# dram.net
KiCad netlist of a schematic drawn in Altium Designer
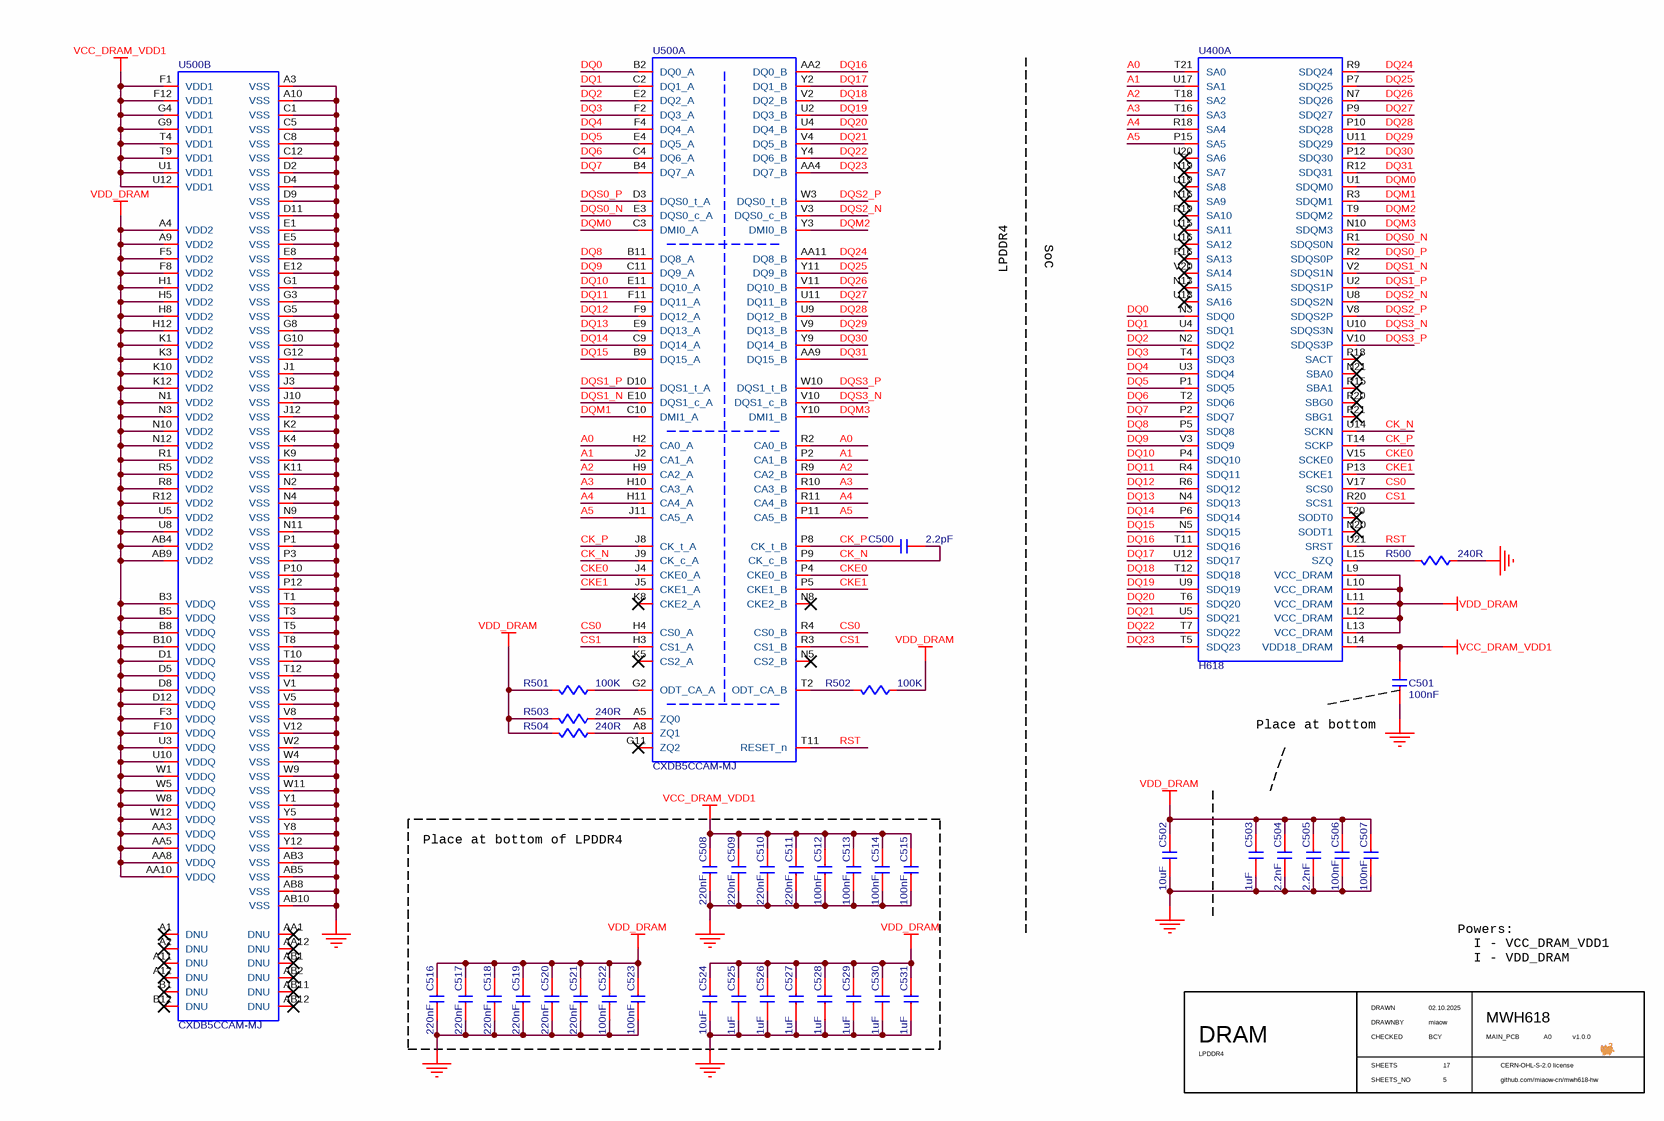
[diagram p0: dram.schdoc]

(export (version "E")
  (design (tool "Eeschema 10.0.6"))
  (components
    (comp (ref "C500")
      (value "2.2pF")
      (footprint "mw:C0201")
      (fields (field (name "VOLTAGE") "25V") (field (name "Comment") "C-NOMO"))
      (libsource (lib "mw") (part "C-NOMO"))
    )
    (comp (ref "C501")
      (value "100nF")
      (footprint "mw:C0201")
      (fields (field (name "VOLTAGE") "10V") (field (name "Comment") "C-NOMO"))
      (libsource (lib "mw") (part "C-NOMO"))
    )
    (comp (ref "C502")
      (value "10uF")
      (footprint "mw:C0402")
      (fields (field (name "VOLTAGE") "6.3V") (field (name "Comment") "C-NOMO"))
      (libsource (lib "mw") (part "C-NOMO"))
    )
    (comp (ref "C503")
      (value "1uF")
      (footprint "mw:C0201")
      (fields (field (name "VOLTAGE") "6.3V") (field (name "Comment") "C-NOMO"))
      (libsource (lib "mw") (part "C-NOMO"))
    )
    (comp (ref "C504")
      (value "2.2nF")
      (footprint "mw:C0201")
      (fields (field (name "VOLTAGE") "50V") (field (name "Comment") "C-NOMO"))
      (libsource (lib "mw") (part "C-NOMO"))
    )
    (comp (ref "C505")
      (value "2.2nF")
      (footprint "mw:C0201")
      (fields (field (name "VOLTAGE") "50V") (field (name "Comment") "C-NOMO"))
      (libsource (lib "mw") (part "C-NOMO"))
    )
    (comp (ref "C506")
      (value "100nF")
      (footprint "mw:C0201")
      (fields (field (name "VOLTAGE") "10V") (field (name "Comment") "C-NOMO"))
      (libsource (lib "mw") (part "C-NOMO"))
    )
    (comp (ref "C507")
      (value "100nF")
      (footprint "mw:C0201")
      (fields (field (name "VOLTAGE") "10V") (field (name "Comment") "C-NOMO"))
      (libsource (lib "mw") (part "C-NOMO"))
    )
    (comp (ref "C508")
      (value "220nF")
      (footprint "mw:C0201")
      (fields (field (name "VOLTAGE") "6.3V") (field (name "Comment") "C-NOMO"))
      (libsource (lib "mw") (part "C-NOMO"))
    )
    (comp (ref "C509")
      (value "220nF")
      (footprint "mw:C0201")
      (fields (field (name "VOLTAGE") "6.3V") (field (name "Comment") "C-NOMO"))
      (libsource (lib "mw") (part "C-NOMO"))
    )
    (comp (ref "C510")
      (value "220nF")
      (footprint "mw:C0201")
      (fields (field (name "VOLTAGE") "6.3V") (field (name "Comment") "C-NOMO"))
      (libsource (lib "mw") (part "C-NOMO"))
    )
    (comp (ref "C511")
      (value "220nF")
      (footprint "mw:C0201")
      (fields (field (name "VOLTAGE") "6.3V") (field (name "Comment") "C-NOMO"))
      (libsource (lib "mw") (part "C-NOMO"))
    )
    (comp (ref "C512")
      (value "100nF")
      (footprint "mw:C0201")
      (fields (field (name "VOLTAGE") "10V") (field (name "Comment") "C-NOMO"))
      (libsource (lib "mw") (part "C-NOMO"))
    )
    (comp (ref "C513")
      (value "100nF")
      (footprint "mw:C0201")
      (fields (field (name "VOLTAGE") "10V") (field (name "Comment") "C-NOMO"))
      (libsource (lib "mw") (part "C-NOMO"))
    )
    (comp (ref "C514")
      (value "100nF")
      (footprint "mw:C0201")
      (fields (field (name "VOLTAGE") "10V") (field (name "Comment") "C-NOMO"))
      (libsource (lib "mw") (part "C-NOMO"))
    )
    (comp (ref "C515")
      (value "100nF")
      (footprint "mw:C0201")
      (fields (field (name "VOLTAGE") "10V") (field (name "Comment") "C-NOMO"))
      (libsource (lib "mw") (part "C-NOMO"))
    )
    (comp (ref "C516")
      (value "220nF")
      (footprint "mw:C0201")
      (fields (field (name "VOLTAGE") "6.3V") (field (name "Comment") "C-NOMO"))
      (libsource (lib "mw") (part "C-NOMO"))
    )
    (comp (ref "C517")
      (value "220nF")
      (footprint "mw:C0201")
      (fields (field (name "VOLTAGE") "6.3V") (field (name "Comment") "C-NOMO"))
      (libsource (lib "mw") (part "C-NOMO"))
    )
    (comp (ref "C518")
      (value "220nF")
      (footprint "mw:C0201")
      (fields (field (name "VOLTAGE") "6.3V") (field (name "Comment") "C-NOMO"))
      (libsource (lib "mw") (part "C-NOMO"))
    )
    (comp (ref "C519")
      (value "220nF")
      (footprint "mw:C0201")
      (fields (field (name "VOLTAGE") "6.3V") (field (name "Comment") "C-NOMO"))
      (libsource (lib "mw") (part "C-NOMO"))
    )
    (comp (ref "C520")
      (value "220nF")
      (footprint "mw:C0201")
      (fields (field (name "VOLTAGE") "6.3V") (field (name "Comment") "C-NOMO"))
      (libsource (lib "mw") (part "C-NOMO"))
    )
    (comp (ref "C521")
      (value "220nF")
      (footprint "mw:C0201")
      (fields (field (name "VOLTAGE") "6.3V") (field (name "Comment") "C-NOMO"))
      (libsource (lib "mw") (part "C-NOMO"))
    )
    (comp (ref "C522")
      (value "100nF")
      (footprint "mw:C0201")
      (fields (field (name "VOLTAGE") "10V") (field (name "Comment") "C-NOMO"))
      (libsource (lib "mw") (part "C-NOMO"))
    )
    (comp (ref "C523")
      (value "100nF")
      (footprint "mw:C0201")
      (fields (field (name "VOLTAGE") "10V") (field (name "Comment") "C-NOMO"))
      (libsource (lib "mw") (part "C-NOMO"))
    )
    (comp (ref "C524")
      (value "10uF")
      (footprint "mw:C0402")
      (fields (field (name "VOLTAGE") "6.3V") (field (name "Comment") "C-NOMO"))
      (libsource (lib "mw") (part "C-NOMO"))
    )
    (comp (ref "C525")
      (value "1uF")
      (footprint "mw:C0201")
      (fields (field (name "VOLTAGE") "6.3V") (field (name "Comment") "C-NOMO"))
      (libsource (lib "mw") (part "C-NOMO"))
    )
    (comp (ref "C526")
      (value "1uF")
      (footprint "mw:C0201")
      (fields (field (name "VOLTAGE") "6.3V") (field (name "Comment") "C-NOMO"))
      (libsource (lib "mw") (part "C-NOMO"))
    )
    (comp (ref "C527")
      (value "1uF")
      (footprint "mw:C0201")
      (fields (field (name "VOLTAGE") "6.3V") (field (name "Comment") "C-NOMO"))
      (libsource (lib "mw") (part "C-NOMO"))
    )
    (comp (ref "C528")
      (value "1uF")
      (footprint "mw:C0201")
      (fields (field (name "VOLTAGE") "6.3V") (field (name "Comment") "C-NOMO"))
      (libsource (lib "mw") (part "C-NOMO"))
    )
    (comp (ref "C529")
      (value "1uF")
      (footprint "mw:C0201")
      (fields (field (name "VOLTAGE") "6.3V") (field (name "Comment") "C-NOMO"))
      (libsource (lib "mw") (part "C-NOMO"))
    )
    (comp (ref "C530")
      (value "1uF")
      (footprint "mw:C0201")
      (fields (field (name "VOLTAGE") "6.3V") (field (name "Comment") "C-NOMO"))
      (libsource (lib "mw") (part "C-NOMO"))
    )
    (comp (ref "C531")
      (value "1uF")
      (footprint "mw:C0201")
      (fields (field (name "VOLTAGE") "6.3V") (field (name "Comment") "C-NOMO"))
      (libsource (lib "mw") (part "C-NOMO"))
    )
    (comp (ref "R500")
      (value "240R")
      (footprint "mw:R0402")
      (fields (field (name "Comment") "R"))
      (libsource (lib "mw") (part "R"))
    )
    (comp (ref "R501")
      (value "100K")
      (footprint "mw:R0402")
      (fields (field (name "Comment") "R"))
      (libsource (lib "mw") (part "R"))
    )
    (comp (ref "R502")
      (value "100K")
      (footprint "mw:R0402")
      (fields (field (name "Comment") "R"))
      (libsource (lib "mw") (part "R"))
    )
    (comp (ref "R503")
      (value "240R")
      (footprint "mw:R0402")
      (fields (field (name "Comment") "R"))
      (libsource (lib "mw") (part "R"))
    )
    (comp (ref "R504")
      (value "240R")
      (footprint "mw:R0402")
      (fields (field (name "Comment") "R"))
      (libsource (lib "mw") (part "R"))
    )
    (comp (ref "U400")
      (value "H618")
      (footprint "mw:H618")
      (description "SOC")
      (libsource (lib "mw") (part "H618"))
    )
    (comp (ref "U500")
      (value "CXDB5CCAM-MJ")
      (footprint "mw:CXDB5CCAM-MJ")
      (description "DDR - LPDDR4")
      (libsource (lib "mw") (part "CXDB5CCAM-MJ"))
    )
  )
  (nets
    (net (code "1") (name "/A0") (class "Default")
      (node (ref "U400") (pin "T21") (pinfunction "SA0_T21") (pintype "passive"))
      (node (ref "U500") (pin "H2") (pinfunction "CA0_A_H2") (pintype "passive"))
      (node (ref "U500") (pin "R2") (pinfunction "CA0_B_R2") (pintype "passive"))
    )
    (net (code "2") (name "/A1") (class "Default")
      (node (ref "U400") (pin "U17") (pinfunction "SA1_U17") (pintype "passive"))
      (node (ref "U500") (pin "J2") (pinfunction "CA1_A_J2") (pintype "passive"))
      (node (ref "U500") (pin "P2") (pinfunction "CA1_B_P2") (pintype "passive"))
    )
    (net (code "3") (name "/A2") (class "Default")
      (node (ref "U400") (pin "T18") (pinfunction "SA2_T18") (pintype "passive"))
      (node (ref "U500") (pin "H9") (pinfunction "CA2_A_H9") (pintype "passive"))
      (node (ref "U500") (pin "R9") (pinfunction "CA2_B_R9") (pintype "passive"))
    )
    (net (code "4") (name "/A3") (class "Default")
      (node (ref "U400") (pin "T16") (pinfunction "SA3_T16") (pintype "passive"))
      (node (ref "U500") (pin "H10") (pinfunction "CA3_A_H10") (pintype "passive"))
      (node (ref "U500") (pin "R10") (pinfunction "CA3_B_R10") (pintype "passive"))
    )
    (net (code "5") (name "/A4") (class "Default")
      (node (ref "U400") (pin "R18") (pinfunction "SA4_R18") (pintype "passive"))
      (node (ref "U500") (pin "H11") (pinfunction "CA4_A_H11") (pintype "passive"))
      (node (ref "U500") (pin "R11") (pinfunction "CA4_B_R11") (pintype "passive"))
    )
    (net (code "6") (name "/A5") (class "Default")
      (node (ref "U400") (pin "P15") (pinfunction "SA5_P15") (pintype "passive"))
      (node (ref "U500") (pin "J11") (pinfunction "CA5_A_J11") (pintype "passive"))
      (node (ref "U500") (pin "P11") (pinfunction "CA5_B_P11") (pintype "passive"))
    )
    (net (code "7") (name "/CKE0") (class "Default")
      (node (ref "U400") (pin "V15") (pinfunction "SCKE0_V15") (pintype "passive"))
      (node (ref "U500") (pin "J4") (pinfunction "CKE0_A_J4") (pintype "passive"))
      (node (ref "U500") (pin "P4") (pinfunction "CKE0_B_P4") (pintype "passive"))
    )
    (net (code "8") (name "/CKE1") (class "Default")
      (node (ref "U400") (pin "P13") (pinfunction "SCKE1_P13") (pintype "passive"))
      (node (ref "U500") (pin "J5") (pinfunction "CKE1_A_J5") (pintype "passive"))
      (node (ref "U500") (pin "P5") (pinfunction "CKE1_B_P5") (pintype "passive"))
    )
    (net (code "9") (name "/CK_N") (class "Default")
      (node (ref "C500") (pin "1") (pinfunction "1_1") (pintype "passive"))
      (node (ref "U400") (pin "U14") (pinfunction "SCKN_U14") (pintype "passive"))
      (node (ref "U500") (pin "J9") (pinfunction "CK_c_A_J9") (pintype "passive"))
      (node (ref "U500") (pin "P9") (pinfunction "CK_c_B_P9") (pintype "passive"))
    )
    (net (code "10") (name "/CK_P") (class "Default")
      (node (ref "C500") (pin "2") (pinfunction "2_2") (pintype "passive"))
      (node (ref "U400") (pin "T14") (pinfunction "SCKP_T14") (pintype "passive"))
      (node (ref "U500") (pin "J8") (pinfunction "CK_t_A_J8") (pintype "passive"))
      (node (ref "U500") (pin "P8") (pinfunction "CK_t_B_P8") (pintype "passive"))
    )
    (net (code "11") (name "/CS0") (class "Default")
      (node (ref "U400") (pin "V17") (pinfunction "SCS0_V17") (pintype "passive"))
      (node (ref "U500") (pin "H4") (pinfunction "CS0_A_H4") (pintype "passive"))
      (node (ref "U500") (pin "R4") (pinfunction "CS0_B_R4") (pintype "passive"))
    )
    (net (code "12") (name "/CS1") (class "Default")
      (node (ref "U400") (pin "R20") (pinfunction "SCS1_R20") (pintype "passive"))
      (node (ref "U500") (pin "H3") (pinfunction "CS1_A_H3") (pintype "passive"))
      (node (ref "U500") (pin "R3") (pinfunction "CS1_B_R3") (pintype "passive"))
    )
    (net (code "13") (name "/DQ0") (class "Default")
      (node (ref "U400") (pin "N3") (pinfunction "SDQ0_N3") (pintype "passive"))
      (node (ref "U500") (pin "B2") (pinfunction "DQ0_A_B2") (pintype "passive"))
    )
    (net (code "14") (name "/DQ1") (class "Default")
      (node (ref "U400") (pin "U4") (pinfunction "SDQ1_U4") (pintype "passive"))
      (node (ref "U500") (pin "C2") (pinfunction "DQ1_A_C2") (pintype "passive"))
    )
    (net (code "15") (name "/DQ2") (class "Default")
      (node (ref "U400") (pin "N2") (pinfunction "SDQ2_N2") (pintype "passive"))
      (node (ref "U500") (pin "E2") (pinfunction "DQ2_A_E2") (pintype "passive"))
    )
    (net (code "16") (name "/DQ3") (class "Default")
      (node (ref "U400") (pin "T4") (pinfunction "SDQ3_T4") (pintype "passive"))
      (node (ref "U500") (pin "F2") (pinfunction "DQ3_A_F2") (pintype "passive"))
    )
    (net (code "17") (name "/DQ4") (class "Default")
      (node (ref "U400") (pin "U3") (pinfunction "SDQ4_U3") (pintype "passive"))
      (node (ref "U500") (pin "F4") (pinfunction "DQ4_A_F4") (pintype "passive"))
    )
    (net (code "18") (name "/DQ5") (class "Default")
      (node (ref "U400") (pin "P1") (pinfunction "SDQ5_P1") (pintype "passive"))
      (node (ref "U500") (pin "E4") (pinfunction "DQ5_A_E4") (pintype "passive"))
    )
    (net (code "19") (name "/DQ6") (class "Default")
      (node (ref "U400") (pin "T2") (pinfunction "SDQ6_T2") (pintype "passive"))
      (node (ref "U500") (pin "C4") (pinfunction "DQ6_A_C4") (pintype "passive"))
    )
    (net (code "20") (name "/DQ7") (class "Default")
      (node (ref "U400") (pin "P2") (pinfunction "SDQ7_P2") (pintype "passive"))
      (node (ref "U500") (pin "B4") (pinfunction "DQ7_A_B4") (pintype "passive"))
    )
    (net (code "21") (name "/DQ8") (class "Default")
      (node (ref "U400") (pin "P5") (pinfunction "SDQ8_P5") (pintype "passive"))
      (node (ref "U500") (pin "B11") (pinfunction "DQ8_A_B11") (pintype "passive"))
    )
    (net (code "22") (name "/DQ9") (class "Default")
      (node (ref "U400") (pin "V3") (pinfunction "SDQ9_V3") (pintype "passive"))
      (node (ref "U500") (pin "C11") (pinfunction "DQ9_A_C11") (pintype "passive"))
    )
    (net (code "23") (name "/DQ10") (class "Default")
      (node (ref "U400") (pin "P4") (pinfunction "SDQ10_P4") (pintype "passive"))
      (node (ref "U500") (pin "E11") (pinfunction "DQ10_A_E11") (pintype "passive"))
    )
    (net (code "24") (name "/DQ11") (class "Default")
      (node (ref "U400") (pin "R4") (pinfunction "SDQ11_R4") (pintype "passive"))
      (node (ref "U500") (pin "F11") (pinfunction "DQ11_A_F11") (pintype "passive"))
    )
    (net (code "25") (name "/DQ12") (class "Default")
      (node (ref "U400") (pin "R6") (pinfunction "SDQ12_R6") (pintype "passive"))
      (node (ref "U500") (pin "F9") (pinfunction "DQ12_A_F9") (pintype "passive"))
    )
    (net (code "26") (name "/DQ13") (class "Default")
      (node (ref "U400") (pin "N4") (pinfunction "SDQ13_N4") (pintype "passive"))
      (node (ref "U500") (pin "E9") (pinfunction "DQ13_A_E9") (pintype "passive"))
    )
    (net (code "27") (name "/DQ14") (class "Default")
      (node (ref "U400") (pin "P6") (pinfunction "SDQ14_P6") (pintype "passive"))
      (node (ref "U500") (pin "C9") (pinfunction "DQ14_A_C9") (pintype "passive"))
    )
    (net (code "28") (name "/DQ15") (class "Default")
      (node (ref "U400") (pin "N5") (pinfunction "SDQ15_N5") (pintype "passive"))
      (node (ref "U500") (pin "B9") (pinfunction "DQ15_A_B9") (pintype "passive"))
    )
    (net (code "29") (name "/DQ16") (class "Default")
      (node (ref "U400") (pin "T11") (pinfunction "SDQ16_T11") (pintype "passive"))
      (node (ref "U500") (pin "AA2") (pinfunction "DQ0_B_AA2") (pintype "passive"))
    )
    (net (code "30") (name "/DQ17") (class "Default")
      (node (ref "U400") (pin "U12") (pinfunction "SDQ17_U12") (pintype "passive"))
      (node (ref "U500") (pin "Y2") (pinfunction "DQ1_B_Y2") (pintype "passive"))
    )
    (net (code "31") (name "/DQ18") (class "Default")
      (node (ref "U400") (pin "T12") (pinfunction "SDQ18_T12") (pintype "passive"))
      (node (ref "U500") (pin "V2") (pinfunction "DQ2_B_V2") (pintype "passive"))
    )
    (net (code "32") (name "/DQ19") (class "Default")
      (node (ref "U400") (pin "U9") (pinfunction "SDQ19_U9") (pintype "passive"))
      (node (ref "U500") (pin "U2") (pinfunction "DQ3_B_U2") (pintype "passive"))
    )
    (net (code "33") (name "/DQ20") (class "Default")
      (node (ref "U400") (pin "T6") (pinfunction "SDQ20_T6") (pintype "passive"))
      (node (ref "U500") (pin "U4") (pinfunction "DQ4_B_U4") (pintype "passive"))
    )
    (net (code "34") (name "/DQ21") (class "Default")
      (node (ref "U400") (pin "U5") (pinfunction "SDQ21_U5") (pintype "passive"))
      (node (ref "U500") (pin "V4") (pinfunction "DQ5_B_V4") (pintype "passive"))
    )
    (net (code "35") (name "/DQ22") (class "Default")
      (node (ref "U400") (pin "T7") (pinfunction "SDQ22_T7") (pintype "passive"))
      (node (ref "U500") (pin "Y4") (pinfunction "DQ6_B_Y4") (pintype "passive"))
    )
    (net (code "36") (name "/DQ23") (class "Default")
      (node (ref "U400") (pin "T5") (pinfunction "SDQ23_T5") (pintype "passive"))
      (node (ref "U500") (pin "AA4") (pinfunction "DQ7_B_AA4") (pintype "passive"))
    )
    (net (code "37") (name "/DQ24") (class "Default")
      (node (ref "U400") (pin "R9") (pinfunction "SDQ24_R9") (pintype "passive"))
      (node (ref "U500") (pin "AA11") (pinfunction "DQ8_B_AA11") (pintype "passive"))
    )
    (net (code "38") (name "/DQ25") (class "Default")
      (node (ref "U400") (pin "P7") (pinfunction "SDQ25_P7") (pintype "passive"))
      (node (ref "U500") (pin "Y11") (pinfunction "DQ9_B_Y11") (pintype "passive"))
    )
    (net (code "39") (name "/DQ26") (class "Default")
      (node (ref "U400") (pin "N7") (pinfunction "SDQ26_N7") (pintype "passive"))
      (node (ref "U500") (pin "V11") (pinfunction "DQ10_B_V11") (pintype "passive"))
    )
    (net (code "40") (name "/DQ27") (class "Default")
      (node (ref "U400") (pin "P9") (pinfunction "SDQ27_P9") (pintype "passive"))
      (node (ref "U500") (pin "U11") (pinfunction "DQ11_B_U11") (pintype "passive"))
    )
    (net (code "41") (name "/DQ28") (class "Default")
      (node (ref "U400") (pin "P10") (pinfunction "SDQ28_P10") (pintype "passive"))
      (node (ref "U500") (pin "U9") (pinfunction "DQ12_B_U9") (pintype "passive"))
    )
    (net (code "42") (name "/DQ29") (class "Default")
      (node (ref "U400") (pin "U11") (pinfunction "SDQ29_U11") (pintype "passive"))
      (node (ref "U500") (pin "V9") (pinfunction "DQ13_B_V9") (pintype "passive"))
    )
    (net (code "43") (name "/DQ30") (class "Default")
      (node (ref "U400") (pin "P12") (pinfunction "SDQ30_P12") (pintype "passive"))
      (node (ref "U500") (pin "Y9") (pinfunction "DQ14_B_Y9") (pintype "passive"))
    )
    (net (code "44") (name "/DQ31") (class "Default")
      (node (ref "U400") (pin "R12") (pinfunction "SDQ31_R12") (pintype "passive"))
      (node (ref "U500") (pin "AA9") (pinfunction "DQ15_B_AA9") (pintype "passive"))
    )
    (net (code "45") (name "/DQM0") (class "Default")
      (node (ref "U400") (pin "U1") (pinfunction "SDQM0_U1") (pintype "passive"))
      (node (ref "U500") (pin "C3") (pinfunction "DMI0_A_C3") (pintype "passive"))
    )
    (net (code "46") (name "/DQM1") (class "Default")
      (node (ref "U400") (pin "R3") (pinfunction "SDQM1_R3") (pintype "passive"))
      (node (ref "U500") (pin "C10") (pinfunction "DMI1_A_C10") (pintype "passive"))
    )
    (net (code "47") (name "/DQM2") (class "Default")
      (node (ref "U400") (pin "T9") (pinfunction "SDQM2_T9") (pintype "passive"))
      (node (ref "U500") (pin "Y3") (pinfunction "DMI0_B_Y3") (pintype "passive"))
    )
    (net (code "48") (name "/DQM3") (class "Default")
      (node (ref "U400") (pin "N10") (pinfunction "SDQM3_N10") (pintype "passive"))
      (node (ref "U500") (pin "Y10") (pinfunction "DMI1_B_Y10") (pintype "passive"))
    )
    (net (code "49") (name "/DQS0_N") (class "Default")
      (node (ref "U400") (pin "R1") (pinfunction "SDQS0N_R1") (pintype "passive"))
      (node (ref "U500") (pin "E3") (pinfunction "DQS0_c_A_E3") (pintype "passive"))
    )
    (net (code "50") (name "/DQS0_P") (class "Default")
      (node (ref "U400") (pin "R2") (pinfunction "SDQS0P_R2") (pintype "passive"))
      (node (ref "U500") (pin "D3") (pinfunction "DQS0_t_A_D3") (pintype "passive"))
    )
    (net (code "51") (name "/DQS1_N") (class "Default")
      (node (ref "U400") (pin "V2") (pinfunction "SDQS1N_V2") (pintype "passive"))
      (node (ref "U500") (pin "E10") (pinfunction "DQS1_c_A_E10") (pintype "passive"))
    )
    (net (code "52") (name "/DQS1_P") (class "Default")
      (node (ref "U400") (pin "U2") (pinfunction "SDQS1P_U2") (pintype "passive"))
      (node (ref "U500") (pin "D10") (pinfunction "DQS1_t_A_D10") (pintype "passive"))
    )
    (net (code "53") (name "/DQS2_N") (class "Default")
      (node (ref "U400") (pin "U8") (pinfunction "SDQS2N_U8") (pintype "passive"))
      (node (ref "U500") (pin "V3") (pinfunction "DQS0_c_B_V3") (pintype "passive"))
    )
    (net (code "54") (name "/DQS2_P") (class "Default")
      (node (ref "U400") (pin "V8") (pinfunction "SDQS2P_V8") (pintype "passive"))
      (node (ref "U500") (pin "W3") (pinfunction "DQS0_t_B_W3") (pintype "passive"))
    )
    (net (code "55") (name "/DQS3_N") (class "Default")
      (node (ref "U400") (pin "U10") (pinfunction "SDQS3N_U10") (pintype "passive"))
      (node (ref "U500") (pin "V10") (pinfunction "DQS1_c_B_V10") (pintype "passive"))
    )
    (net (code "56") (name "/DQS3_P") (class "Default")
      (node (ref "U400") (pin "V10") (pinfunction "SDQS3P_V10") (pintype "passive"))
      (node (ref "U500") (pin "W10") (pinfunction "DQS1_t_B_W10") (pintype "passive"))
    )
    (net (code "57") (name "/RST") (class "Default")
      (node (ref "U400") (pin "U21") (pinfunction "SRST_U21") (pintype "passive"))
      (node (ref "U500") (pin "T11") (pinfunction "RESET_n_T11") (pintype "passive"))
    )
    (net (code "58") (name "GND") (class "Default")
      (node (ref "C501") (pin "1") (pinfunction "1_1") (pintype "passive"))
      (node (ref "C502") (pin "1") (pinfunction "1_1") (pintype "passive"))
      (node (ref "C503") (pin "1") (pinfunction "1_1") (pintype "passive"))
      (node (ref "C504") (pin "1") (pinfunction "1_1") (pintype "passive"))
      (node (ref "C505") (pin "1") (pinfunction "1_1") (pintype "passive"))
      (node (ref "C506") (pin "1") (pinfunction "1_1") (pintype "passive"))
      (node (ref "C507") (pin "1") (pinfunction "1_1") (pintype "passive"))
      (node (ref "C508") (pin "1") (pinfunction "1_1") (pintype "passive"))
      (node (ref "C509") (pin "1") (pinfunction "1_1") (pintype "passive"))
      (node (ref "C510") (pin "1") (pinfunction "1_1") (pintype "passive"))
      (node (ref "C511") (pin "1") (pinfunction "1_1") (pintype "passive"))
      (node (ref "C512") (pin "1") (pinfunction "1_1") (pintype "passive"))
      (node (ref "C513") (pin "1") (pinfunction "1_1") (pintype "passive"))
      (node (ref "C514") (pin "1") (pinfunction "1_1") (pintype "passive"))
      (node (ref "C515") (pin "1") (pinfunction "1_1") (pintype "passive"))
      (node (ref "C516") (pin "1") (pinfunction "1_1") (pintype "passive"))
      (node (ref "C517") (pin "1") (pinfunction "1_1") (pintype "passive"))
      (node (ref "C518") (pin "1") (pinfunction "1_1") (pintype "passive"))
      (node (ref "C519") (pin "1") (pinfunction "1_1") (pintype "passive"))
      (node (ref "C520") (pin "1") (pinfunction "1_1") (pintype "passive"))
      (node (ref "C521") (pin "1") (pinfunction "1_1") (pintype "passive"))
      (node (ref "C522") (pin "1") (pinfunction "1_1") (pintype "passive"))
      (node (ref "C523") (pin "1") (pinfunction "1_1") (pintype "passive"))
      (node (ref "C524") (pin "1") (pinfunction "1_1") (pintype "passive"))
      (node (ref "C525") (pin "1") (pinfunction "1_1") (pintype "passive"))
      (node (ref "C526") (pin "1") (pinfunction "1_1") (pintype "passive"))
      (node (ref "C527") (pin "1") (pinfunction "1_1") (pintype "passive"))
      (node (ref "C528") (pin "1") (pinfunction "1_1") (pintype "passive"))
      (node (ref "C529") (pin "1") (pinfunction "1_1") (pintype "passive"))
      (node (ref "C530") (pin "1") (pinfunction "1_1") (pintype "passive"))
      (node (ref "C531") (pin "1") (pinfunction "1_1") (pintype "passive"))
      (node (ref "R500") (pin "2") (pinfunction "2_2") (pintype "passive"))
      (node (ref "U500") (pin "A10") (pinfunction "VSS_A10") (pintype "passive"))
      (node (ref "U500") (pin "A3") (pinfunction "VSS_A3") (pintype "passive"))
      (node (ref "U500") (pin "AB10") (pinfunction "VSS_AB10") (pintype "passive"))
      (node (ref "U500") (pin "AB3") (pinfunction "VSS_AB3") (pintype "passive"))
      (node (ref "U500") (pin "AB5") (pinfunction "VSS_AB5") (pintype "passive"))
      (node (ref "U500") (pin "AB8") (pinfunction "VSS_AB8") (pintype "passive"))
      (node (ref "U500") (pin "C1") (pinfunction "VSS_C1") (pintype "passive"))
      (node (ref "U500") (pin "C12") (pinfunction "VSS_C12") (pintype "passive"))
      (node (ref "U500") (pin "C5") (pinfunction "VSS_C5") (pintype "passive"))
      (node (ref "U500") (pin "C8") (pinfunction "VSS_C8") (pintype "passive"))
      (node (ref "U500") (pin "D11") (pinfunction "VSS_D11") (pintype "passive"))
      (node (ref "U500") (pin "D2") (pinfunction "VSS_D2") (pintype "passive"))
      (node (ref "U500") (pin "D4") (pinfunction "VSS_D4") (pintype "passive"))
      (node (ref "U500") (pin "D9") (pinfunction "VSS_D9") (pintype "passive"))
      (node (ref "U500") (pin "E1") (pinfunction "VSS_E1") (pintype "passive"))
      (node (ref "U500") (pin "E12") (pinfunction "VSS_E12") (pintype "passive"))
      (node (ref "U500") (pin "E5") (pinfunction "VSS_E5") (pintype "passive"))
      (node (ref "U500") (pin "E8") (pinfunction "VSS_E8") (pintype "passive"))
      (node (ref "U500") (pin "G1") (pinfunction "VSS_G1") (pintype "passive"))
      (node (ref "U500") (pin "G10") (pinfunction "VSS_G10") (pintype "passive"))
      (node (ref "U500") (pin "G12") (pinfunction "VSS_G12") (pintype "passive"))
      (node (ref "U500") (pin "G3") (pinfunction "VSS_G3") (pintype "passive"))
      (node (ref "U500") (pin "G5") (pinfunction "VSS_G5") (pintype "passive"))
      (node (ref "U500") (pin "G8") (pinfunction "VSS_G8") (pintype "passive"))
      (node (ref "U500") (pin "J1") (pinfunction "VSS_J1") (pintype "passive"))
      (node (ref "U500") (pin "J10") (pinfunction "VSS_J10") (pintype "passive"))
      (node (ref "U500") (pin "J12") (pinfunction "VSS_J12") (pintype "passive"))
      (node (ref "U500") (pin "J3") (pinfunction "VSS_J3") (pintype "passive"))
      (node (ref "U500") (pin "K11") (pinfunction "VSS_K11") (pintype "passive"))
      (node (ref "U500") (pin "K2") (pinfunction "VSS_K2") (pintype "passive"))
      (node (ref "U500") (pin "K4") (pinfunction "VSS_K4") (pintype "passive"))
      (node (ref "U500") (pin "K9") (pinfunction "VSS_K9") (pintype "passive"))
      (node (ref "U500") (pin "N11") (pinfunction "VSS_N11") (pintype "passive"))
      (node (ref "U500") (pin "N2") (pinfunction "VSS_N2") (pintype "passive"))
      (node (ref "U500") (pin "N4") (pinfunction "VSS_N4") (pintype "passive"))
      (node (ref "U500") (pin "N9") (pinfunction "VSS_N9") (pintype "passive"))
      (node (ref "U500") (pin "P1") (pinfunction "VSS_P1") (pintype "passive"))
      (node (ref "U500") (pin "P10") (pinfunction "VSS_P10") (pintype "passive"))
      (node (ref "U500") (pin "P12") (pinfunction "VSS_P12") (pintype "passive"))
      (node (ref "U500") (pin "P3") (pinfunction "VSS_P3") (pintype "passive"))
      (node (ref "U500") (pin "T1") (pinfunction "VSS_T1") (pintype "passive"))
      (node (ref "U500") (pin "T10") (pinfunction "VSS_T10") (pintype "passive"))
      (node (ref "U500") (pin "T12") (pinfunction "VSS_T12") (pintype "passive"))
      (node (ref "U500") (pin "T3") (pinfunction "VSS_T3") (pintype "passive"))
      (node (ref "U500") (pin "T5") (pinfunction "VSS_T5") (pintype "passive"))
      (node (ref "U500") (pin "T8") (pinfunction "VSS_T8") (pintype "passive"))
      (node (ref "U500") (pin "V1") (pinfunction "VSS_V1") (pintype "passive"))
      (node (ref "U500") (pin "V12") (pinfunction "VSS_V12") (pintype "passive"))
      (node (ref "U500") (pin "V5") (pinfunction "VSS_V5") (pintype "passive"))
      (node (ref "U500") (pin "V8") (pinfunction "VSS_V8") (pintype "passive"))
      (node (ref "U500") (pin "W11") (pinfunction "VSS_W11") (pintype "passive"))
      (node (ref "U500") (pin "W2") (pinfunction "VSS_W2") (pintype "passive"))
      (node (ref "U500") (pin "W4") (pinfunction "VSS_W4") (pintype "passive"))
      (node (ref "U500") (pin "W9") (pinfunction "VSS_W9") (pintype "passive"))
      (node (ref "U500") (pin "Y1") (pinfunction "VSS_Y1") (pintype "passive"))
      (node (ref "U500") (pin "Y12") (pinfunction "VSS_Y12") (pintype "passive"))
      (node (ref "U500") (pin "Y5") (pinfunction "VSS_Y5") (pintype "passive"))
      (node (ref "U500") (pin "Y8") (pinfunction "VSS_Y8") (pintype "passive"))
    )
    (net (code "59") (name "Net-(U400A-SZQ)") (class "Default")
      (node (ref "R500") (pin "1") (pinfunction "1_1") (pintype "passive"))
      (node (ref "U400") (pin "L15") (pinfunction "SZQ_L15") (pintype "passive"))
    )
    (net (code "60") (name "Net-(U500A-ODT_CA_A)") (class "Default")
      (node (ref "R501") (pin "2") (pinfunction "2_2") (pintype "passive"))
      (node (ref "U500") (pin "G2") (pinfunction "ODT_CA_A_G2") (pintype "passive"))
    )
    (net (code "61") (name "Net-(U500A-ODT_CA_B)") (class "Default")
      (node (ref "R502") (pin "1") (pinfunction "1_1") (pintype "passive"))
      (node (ref "U500") (pin "T2") (pinfunction "ODT_CA_B_T2") (pintype "passive"))
    )
    (net (code "62") (name "Net-(U500A-ZQ0)") (class "Default")
      (node (ref "R503") (pin "2") (pinfunction "2_2") (pintype "passive"))
      (node (ref "U500") (pin "A5") (pinfunction "ZQ0_A5") (pintype "passive"))
    )
    (net (code "63") (name "Net-(U500A-ZQ1)") (class "Default")
      (node (ref "R504") (pin "2") (pinfunction "2_2") (pintype "passive"))
      (node (ref "U500") (pin "A8") (pinfunction "ZQ1_A8") (pintype "passive"))
    )
    (net (code "64") (name "VCC_DRAM_VDD1") (class "Default")
      (node (ref "C501") (pin "2") (pinfunction "2_2") (pintype "passive"))
      (node (ref "C508") (pin "2") (pinfunction "2_2") (pintype "passive"))
      (node (ref "C509") (pin "2") (pinfunction "2_2") (pintype "passive"))
      (node (ref "C510") (pin "2") (pinfunction "2_2") (pintype "passive"))
      (node (ref "C511") (pin "2") (pinfunction "2_2") (pintype "passive"))
      (node (ref "C512") (pin "2") (pinfunction "2_2") (pintype "passive"))
      (node (ref "C513") (pin "2") (pinfunction "2_2") (pintype "passive"))
      (node (ref "C514") (pin "2") (pinfunction "2_2") (pintype "passive"))
      (node (ref "C515") (pin "2") (pinfunction "2_2") (pintype "passive"))
      (node (ref "U400") (pin "L14") (pinfunction "VDD18_DRAM_L14") (pintype "passive"))
      (node (ref "U500") (pin "F1") (pinfunction "VDD1_F1") (pintype "passive"))
      (node (ref "U500") (pin "F12") (pinfunction "VDD1_F12") (pintype "passive"))
      (node (ref "U500") (pin "G4") (pinfunction "VDD1_G4") (pintype "passive"))
      (node (ref "U500") (pin "G9") (pinfunction "VDD1_G9") (pintype "passive"))
      (node (ref "U500") (pin "T4") (pinfunction "VDD1_T4") (pintype "passive"))
      (node (ref "U500") (pin "T9") (pinfunction "VDD1_T9") (pintype "passive"))
      (node (ref "U500") (pin "U1") (pinfunction "VDD1_U1") (pintype "passive"))
      (node (ref "U500") (pin "U12") (pinfunction "VDD1_U12") (pintype "passive"))
    )
    (net (code "65") (name "VDD_DRAM") (class "Default")
      (node (ref "C502") (pin "2") (pinfunction "2_2") (pintype "passive"))
      (node (ref "C503") (pin "2") (pinfunction "2_2") (pintype "passive"))
      (node (ref "C504") (pin "2") (pinfunction "2_2") (pintype "passive"))
      (node (ref "C505") (pin "2") (pinfunction "2_2") (pintype "passive"))
      (node (ref "C506") (pin "2") (pinfunction "2_2") (pintype "passive"))
      (node (ref "C507") (pin "2") (pinfunction "2_2") (pintype "passive"))
      (node (ref "C516") (pin "2") (pinfunction "2_2") (pintype "passive"))
      (node (ref "C517") (pin "2") (pinfunction "2_2") (pintype "passive"))
      (node (ref "C518") (pin "2") (pinfunction "2_2") (pintype "passive"))
      (node (ref "C519") (pin "2") (pinfunction "2_2") (pintype "passive"))
      (node (ref "C520") (pin "2") (pinfunction "2_2") (pintype "passive"))
      (node (ref "C521") (pin "2") (pinfunction "2_2") (pintype "passive"))
      (node (ref "C522") (pin "2") (pinfunction "2_2") (pintype "passive"))
      (node (ref "C523") (pin "2") (pinfunction "2_2") (pintype "passive"))
      (node (ref "C524") (pin "2") (pinfunction "2_2") (pintype "passive"))
      (node (ref "C525") (pin "2") (pinfunction "2_2") (pintype "passive"))
      (node (ref "C526") (pin "2") (pinfunction "2_2") (pintype "passive"))
      (node (ref "C527") (pin "2") (pinfunction "2_2") (pintype "passive"))
      (node (ref "C528") (pin "2") (pinfunction "2_2") (pintype "passive"))
      (node (ref "C529") (pin "2") (pinfunction "2_2") (pintype "passive"))
      (node (ref "C530") (pin "2") (pinfunction "2_2") (pintype "passive"))
      (node (ref "C531") (pin "2") (pinfunction "2_2") (pintype "passive"))
      (node (ref "R501") (pin "1") (pinfunction "1_1") (pintype "passive"))
      (node (ref "R502") (pin "2") (pinfunction "2_2") (pintype "passive"))
      (node (ref "R503") (pin "1") (pinfunction "1_1") (pintype "passive"))
      (node (ref "R504") (pin "1") (pinfunction "1_1") (pintype "passive"))
      (node (ref "U400") (pin "L10") (pinfunction "VCC_DRAM_L10") (pintype "passive"))
      (node (ref "U400") (pin "L11") (pinfunction "VCC_DRAM_L11") (pintype "passive"))
      (node (ref "U400") (pin "L12") (pinfunction "VCC_DRAM_L12") (pintype "passive"))
      (node (ref "U400") (pin "L13") (pinfunction "VCC_DRAM_L13") (pintype "passive"))
      (node (ref "U400") (pin "L9") (pinfunction "VCC_DRAM_L9") (pintype "passive"))
      (node (ref "U500") (pin "A4") (pinfunction "VDD2_A4") (pintype "passive"))
      (node (ref "U500") (pin "A9") (pinfunction "VDD2_A9") (pintype "passive"))
      (node (ref "U500") (pin "AA10") (pinfunction "VDDQ_AA10") (pintype "passive"))
      (node (ref "U500") (pin "AA3") (pinfunction "VDDQ_AA3") (pintype "passive"))
      (node (ref "U500") (pin "AA5") (pinfunction "VDDQ_AA5") (pintype "passive"))
      (node (ref "U500") (pin "AA8") (pinfunction "VDDQ_AA8") (pintype "passive"))
      (node (ref "U500") (pin "AB4") (pinfunction "VDD2_AB4") (pintype "passive"))
      (node (ref "U500") (pin "AB9") (pinfunction "VDD2_AB9") (pintype "passive"))
      (node (ref "U500") (pin "B10") (pinfunction "VDDQ_B10") (pintype "passive"))
      (node (ref "U500") (pin "B3") (pinfunction "VDDQ_B3") (pintype "passive"))
      (node (ref "U500") (pin "B5") (pinfunction "VDDQ_B5") (pintype "passive"))
      (node (ref "U500") (pin "B8") (pinfunction "VDDQ_B8") (pintype "passive"))
      (node (ref "U500") (pin "D1") (pinfunction "VDDQ_D1") (pintype "passive"))
      (node (ref "U500") (pin "D12") (pinfunction "VDDQ_D12") (pintype "passive"))
      (node (ref "U500") (pin "D5") (pinfunction "VDDQ_D5") (pintype "passive"))
      (node (ref "U500") (pin "D8") (pinfunction "VDDQ_D8") (pintype "passive"))
      (node (ref "U500") (pin "F10") (pinfunction "VDDQ_F10") (pintype "passive"))
      (node (ref "U500") (pin "F3") (pinfunction "VDDQ_F3") (pintype "passive"))
      (node (ref "U500") (pin "F5") (pinfunction "VDD2_F5") (pintype "passive"))
      (node (ref "U500") (pin "F8") (pinfunction "VDD2_F8") (pintype "passive"))
      (node (ref "U500") (pin "H1") (pinfunction "VDD2_H1") (pintype "passive"))
      (node (ref "U500") (pin "H12") (pinfunction "VDD2_H12") (pintype "passive"))
      (node (ref "U500") (pin "H5") (pinfunction "VDD2_H5") (pintype "passive"))
      (node (ref "U500") (pin "H8") (pinfunction "VDD2_H8") (pintype "passive"))
      (node (ref "U500") (pin "K1") (pinfunction "VDD2_K1") (pintype "passive"))
      (node (ref "U500") (pin "K10") (pinfunction "VDD2_K10") (pintype "passive"))
      (node (ref "U500") (pin "K12") (pinfunction "VDD2_K12") (pintype "passive"))
      (node (ref "U500") (pin "K3") (pinfunction "VDD2_K3") (pintype "passive"))
      (node (ref "U500") (pin "N1") (pinfunction "VDD2_N1") (pintype "passive"))
      (node (ref "U500") (pin "N10") (pinfunction "VDD2_N10") (pintype "passive"))
      (node (ref "U500") (pin "N12") (pinfunction "VDD2_N12") (pintype "passive"))
      (node (ref "U500") (pin "N3") (pinfunction "VDD2_N3") (pintype "passive"))
      (node (ref "U500") (pin "R1") (pinfunction "VDD2_R1") (pintype "passive"))
      (node (ref "U500") (pin "R12") (pinfunction "VDD2_R12") (pintype "passive"))
      (node (ref "U500") (pin "R5") (pinfunction "VDD2_R5") (pintype "passive"))
      (node (ref "U500") (pin "R8") (pinfunction "VDD2_R8") (pintype "passive"))
      (node (ref "U500") (pin "U10") (pinfunction "VDDQ_U10") (pintype "passive"))
      (node (ref "U500") (pin "U3") (pinfunction "VDDQ_U3") (pintype "passive"))
      (node (ref "U500") (pin "U5") (pinfunction "VDD2_U5") (pintype "passive"))
      (node (ref "U500") (pin "U8") (pinfunction "VDD2_U8") (pintype "passive"))
      (node (ref "U500") (pin "W1") (pinfunction "VDDQ_W1") (pintype "passive"))
      (node (ref "U500") (pin "W12") (pinfunction "VDDQ_W12") (pintype "passive"))
      (node (ref "U500") (pin "W5") (pinfunction "VDDQ_W5") (pintype "passive"))
      (node (ref "U500") (pin "W8") (pinfunction "VDDQ_W8") (pintype "passive"))
    )
    (net (code "66") (name "unconnected-(U400A-SA6-PadU20)") (class "Default")
      (node (ref "U400") (pin "U20") (pinfunction "SA6_U20") (pintype "passive+no_connect"))
    )
    (net (code "67") (name "unconnected-(U400A-SA7-PadN19)") (class "Default")
      (node (ref "U400") (pin "N19") (pinfunction "SA7_N19") (pintype "passive+no_connect"))
    )
    (net (code "68") (name "unconnected-(U400A-SA8-PadU19)") (class "Default")
      (node (ref "U400") (pin "U19") (pinfunction "SA8_U19") (pintype "passive+no_connect"))
    )
    (net (code "69") (name "unconnected-(U400A-SA9-PadN16)") (class "Default")
      (node (ref "U400") (pin "N16") (pinfunction "SA9_N16") (pintype "passive+no_connect"))
    )
    (net (code "70") (name "unconnected-(U400A-SA10-PadR19)") (class "Default")
      (node (ref "U400") (pin "R19") (pinfunction "SA10_R19") (pintype "passive+no_connect"))
    )
    (net (code "71") (name "unconnected-(U400A-SA11-PadU15)") (class "Default")
      (node (ref "U400") (pin "U15") (pinfunction "SA11_U15") (pintype "passive+no_connect"))
    )
    (net (code "72") (name "unconnected-(U400A-SA12-PadU16)") (class "Default")
      (node (ref "U400") (pin "U16") (pinfunction "SA12_U16") (pintype "passive+no_connect"))
    )
    (net (code "73") (name "unconnected-(U400A-SA13-PadP16)") (class "Default")
      (node (ref "U400") (pin "P16") (pinfunction "SA13_P16") (pintype "passive+no_connect"))
    )
    (net (code "74") (name "unconnected-(U400A-SA14-PadV20)") (class "Default")
      (node (ref "U400") (pin "V20") (pinfunction "SA14_V20") (pintype "passive+no_connect"))
    )
    (net (code "75") (name "unconnected-(U400A-SA15-PadN13)") (class "Default")
      (node (ref "U400") (pin "N13") (pinfunction "SA15_N13") (pintype "passive+no_connect"))
    )
    (net (code "76") (name "unconnected-(U400A-SA16-PadU18)") (class "Default")
      (node (ref "U400") (pin "U18") (pinfunction "SA16_U18") (pintype "passive+no_connect"))
    )
    (net (code "77") (name "unconnected-(U400A-SACT-PadP18)") (class "Default")
      (node (ref "U400") (pin "P18") (pinfunction "SACT_P18") (pintype "passive+no_connect"))
    )
    (net (code "78") (name "unconnected-(U400A-SBA0-PadN21)") (class "Default")
      (node (ref "U400") (pin "N21") (pinfunction "SBA0_N21") (pintype "passive+no_connect"))
    )
    (net (code "79") (name "unconnected-(U400A-SBA1-PadR15)") (class "Default")
      (node (ref "U400") (pin "R15") (pinfunction "SBA1_R15") (pintype "passive+no_connect"))
    )
    (net (code "80") (name "unconnected-(U400A-SBG0-PadP20)") (class "Default")
      (node (ref "U400") (pin "P20") (pinfunction "SBG0_P20") (pintype "passive+no_connect"))
    )
    (net (code "81") (name "unconnected-(U400A-SBG1-PadP21)") (class "Default")
      (node (ref "U400") (pin "P21") (pinfunction "SBG1_P21") (pintype "passive+no_connect"))
    )
    (net (code "82") (name "unconnected-(U400A-SODT0-PadT20)") (class "Default")
      (node (ref "U400") (pin "T20") (pinfunction "SODT0_T20") (pintype "passive+no_connect"))
    )
    (net (code "83") (name "unconnected-(U400A-SODT1-PadN20)") (class "Default")
      (node (ref "U400") (pin "N20") (pinfunction "SODT1_N20") (pintype "passive+no_connect"))
    )
    (net (code "84") (name "unconnected-(U500A-CKE2_A-PadK8)") (class "Default")
      (node (ref "U500") (pin "K8") (pinfunction "CKE2_A_K8") (pintype "passive+no_connect"))
    )
    (net (code "85") (name "unconnected-(U500A-CKE2_B-PadN8)") (class "Default")
      (node (ref "U500") (pin "N8") (pinfunction "CKE2_B_N8") (pintype "passive+no_connect"))
    )
    (net (code "86") (name "unconnected-(U500A-CS2_A-PadK5)") (class "Default")
      (node (ref "U500") (pin "K5") (pinfunction "CS2_A_K5") (pintype "passive+no_connect"))
    )
    (net (code "87") (name "unconnected-(U500A-CS2_B-PadN5)") (class "Default")
      (node (ref "U500") (pin "N5") (pinfunction "CS2_B_N5") (pintype "passive+no_connect"))
    )
    (net (code "88") (name "unconnected-(U500A-ZQ2-PadG11)") (class "Default")
      (node (ref "U500") (pin "G11") (pinfunction "ZQ2_G11") (pintype "passive+no_connect"))
    )
    (net (code "89") (name "unconnected-(U500B-DNU-PadA1)") (class "Default")
      (node (ref "U500") (pin "A1") (pinfunction "DNU_A1") (pintype "passive+no_connect"))
    )
    (net (code "90") (name "unconnected-(U500B-DNU-PadA2)") (class "Default")
      (node (ref "U500") (pin "A2") (pinfunction "DNU_A2") (pintype "passive+no_connect"))
    )
    (net (code "91") (name "unconnected-(U500B-DNU-PadA11)") (class "Default")
      (node (ref "U500") (pin "A11") (pinfunction "DNU_A11") (pintype "passive+no_connect"))
    )
    (net (code "92") (name "unconnected-(U500B-DNU-PadA12)") (class "Default")
      (node (ref "U500") (pin "A12") (pinfunction "DNU_A12") (pintype "passive+no_connect"))
    )
    (net (code "93") (name "unconnected-(U500B-DNU-PadAA1)") (class "Default")
      (node (ref "U500") (pin "AA1") (pinfunction "DNU_AA1") (pintype "passive+no_connect"))
    )
    (net (code "94") (name "unconnected-(U500B-DNU-PadAA12)") (class "Default")
      (node (ref "U500") (pin "AA12") (pinfunction "DNU_AA12") (pintype "passive+no_connect"))
    )
    (net (code "95") (name "unconnected-(U500B-DNU-PadAB1)") (class "Default")
      (node (ref "U500") (pin "AB1") (pinfunction "DNU_AB1") (pintype "passive+no_connect"))
    )
    (net (code "96") (name "unconnected-(U500B-DNU-PadAB2)") (class "Default")
      (node (ref "U500") (pin "AB2") (pinfunction "DNU_AB2") (pintype "passive+no_connect"))
    )
    (net (code "97") (name "unconnected-(U500B-DNU-PadAB11)") (class "Default")
      (node (ref "U500") (pin "AB11") (pinfunction "DNU_AB11") (pintype "passive+no_connect"))
    )
    (net (code "98") (name "unconnected-(U500B-DNU-PadAB12)") (class "Default")
      (node (ref "U500") (pin "AB12") (pinfunction "DNU_AB12") (pintype "passive+no_connect"))
    )
    (net (code "99") (name "unconnected-(U500B-DNU-PadB1)") (class "Default")
      (node (ref "U500") (pin "B1") (pinfunction "DNU_B1") (pintype "passive+no_connect"))
    )
    (net (code "100") (name "unconnected-(U500B-DNU-PadB12)") (class "Default")
      (node (ref "U500") (pin "B12") (pinfunction "DNU_B12") (pintype "passive+no_connect"))
    )
  )
)
